# 3_TopLevel.net
KiCad netlist of a schematic drawn in Altium Designer
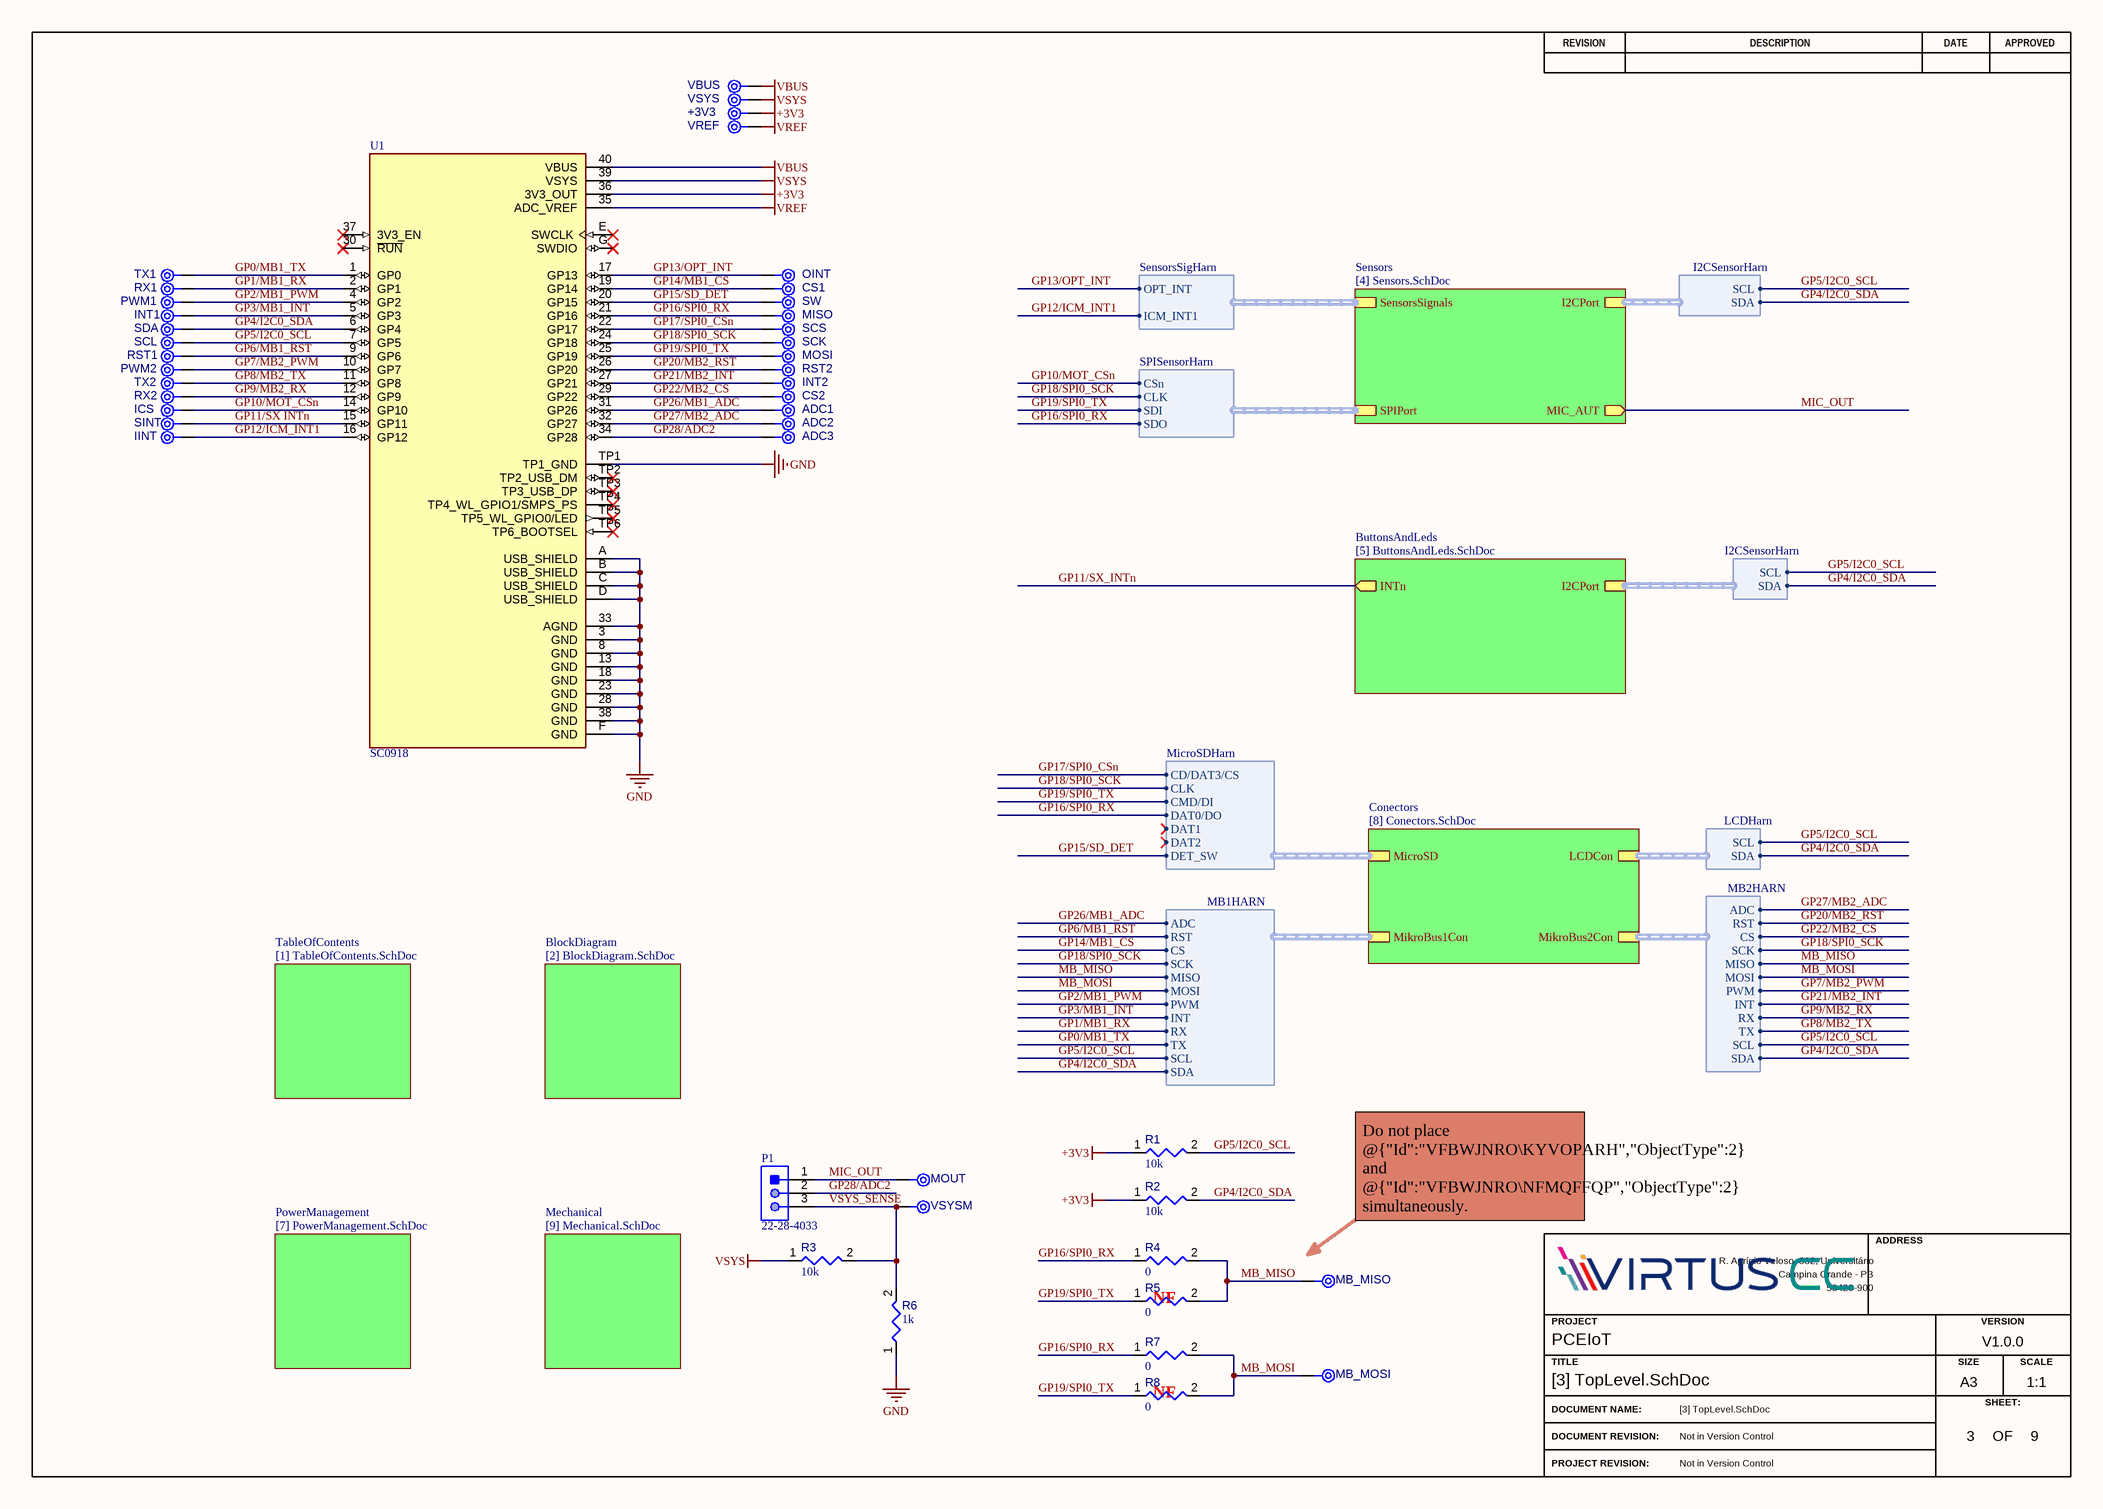
[diagram p0: [3] TopLevel.SchDoc]

(export (version "E")
  (design (tool "Eeschema 10.0.6"))
  (components
    (comp (ref "+3V3")
      (value "TPAD6R")
      (footprint "TP06R")
      (description "0.6mm round")
      (libsource (lib "PCEIOT") (part "CMP-00028-00002-2"))
    )
    (comp (ref "ADC1")
      (value "TPAD6R")
      (footprint "TP06R")
      (description "0.6mm round")
      (libsource (lib "PCEIOT") (part "CMP-00028-00002-2"))
    )
    (comp (ref "ADC2")
      (value "TPAD6R")
      (footprint "TP06R")
      (description "0.6mm round")
      (libsource (lib "PCEIOT") (part "CMP-00028-00002-2"))
    )
    (comp (ref "ADC3")
      (value "TPAD6R")
      (footprint "TP06R")
      (description "0.6mm round")
      (libsource (lib "PCEIOT") (part "CMP-00028-00002-2"))
    )
    (comp (ref "CS1")
      (value "TPAD6R")
      (footprint "TP06R")
      (description "0.6mm round")
      (libsource (lib "PCEIOT") (part "CMP-00028-00002-2"))
    )
    (comp (ref "CS2")
      (value "TPAD6R")
      (footprint "TP06R")
      (description "0.6mm round")
      (libsource (lib "PCEIOT") (part "CMP-00028-00002-2"))
    )
    (comp (ref "ICS")
      (value "TPAD6R")
      (footprint "TP06R")
      (description "0.6mm round")
      (libsource (lib "PCEIOT") (part "CMP-00028-00002-2"))
    )
    (comp (ref "IINT")
      (value "TPAD6R")
      (footprint "TP06R")
      (description "0.6mm round")
      (libsource (lib "PCEIOT") (part "CMP-00028-00002-2"))
    )
    (comp (ref "INT1")
      (value "TPAD6R")
      (footprint "TP06R")
      (description "0.6mm round")
      (libsource (lib "PCEIOT") (part "CMP-00028-00002-2"))
    )
    (comp (ref "INT2")
      (value "TPAD6R")
      (footprint "TP06R")
      (description "0.6mm round")
      (libsource (lib "PCEIOT") (part "CMP-00028-00002-2"))
    )
    (comp (ref "MB_MISO")
      (value "TPAD6R")
      (footprint "TP06R")
      (description "0.6mm round")
      (libsource (lib "PCEIOT") (part "CMP-00028-00002-2"))
    )
    (comp (ref "MB_MOSI")
      (value "TPAD6R")
      (footprint "TP06R")
      (description "0.6mm round")
      (libsource (lib "PCEIOT") (part "CMP-00028-00002-2"))
    )
    (comp (ref "MISO")
      (value "TPAD6R")
      (footprint "TP06R")
      (description "0.6mm round")
      (libsource (lib "PCEIOT") (part "CMP-00028-00002-2"))
    )
    (comp (ref "MOSI")
      (value "TPAD6R")
      (footprint "TP06R")
      (description "0.6mm round")
      (libsource (lib "PCEIOT") (part "CMP-00028-00002-2"))
    )
    (comp (ref "MOUT")
      (value "TPAD6R")
      (footprint "TP06R")
      (description "0.6mm round")
      (libsource (lib "PCEIOT") (part "CMP-00028-00002-2"))
    )
    (comp (ref "OINT")
      (value "TPAD6R")
      (footprint "TP06R")
      (description "0.6mm round")
      (libsource (lib "PCEIOT") (part "CMP-00028-00002-2"))
    )
    (comp (ref "P1")
      (value "22-28-4033")
      (footprint "MOLX-22-28-4033_V")
      (description "KK 254 Breakaway Header Vertical 3 Circuits 0.38um Gold Selective Plating Mating Pin 6.09mm")
      (libsource (lib "UFCG - Universidade Federal de Campina Grande") (part "CN-1P-M-R3"))
    )
    (comp (ref "PWM1")
      (value "TPAD6R")
      (footprint "TP06R")
      (description "0.6mm round")
      (libsource (lib "PCEIOT") (part "CMP-00028-00002-2"))
    )
    (comp (ref "PWM2")
      (value "TPAD6R")
      (footprint "TP06R")
      (description "0.6mm round")
      (libsource (lib "PCEIOT") (part "CMP-00028-00002-2"))
    )
    (comp (ref "R1")
      (value "10k")
      (footprint "RESC0603(1608)_L")
      (description "Chip Resistor, 10 KOhm, +/- 1%, 01 W, -55 to 155 degC, 0603 (1608 Metric)")
      (fields (field (name "POWER") "100mW") (field (name "TOLERANCE") "1%"))
      (libsource (lib "UFCG - Universidade Federal de Campina Grande") (part "RES-2"))
    )
    (comp (ref "R2")
      (value "10k")
      (footprint "RESC0603(1608)_L")
      (description "Chip Resistor, 10 KOhm, +/- 1%, 01 W, -55 to 155 degC, 0603 (1608 Metric)")
      (fields (field (name "POWER") "100mW") (field (name "TOLERANCE") "1%"))
      (libsource (lib "UFCG - Universidade Federal de Campina Grande") (part "RES-2"))
    )
    (comp (ref "R3")
      (value "10k")
      (footprint "RESC0603(1608)_L")
      (description "Chip Resistor, 10 KOhm, +/- 1%, 01 W, -55 to 155 degC, 0603 (1608 Metric)")
      (fields (field (name "POWER") "100mW") (field (name "TOLERANCE") "1%"))
      (libsource (lib "UFCG - Universidade Federal de Campina Grande") (part "RES-2"))
    )
    (comp (ref "R4")
      (value "0")
      (footprint "RESC0603(1608)_L")
      (description "Chip Resistor, 0 Ohm, 0.1 W, -55 to 155 degC, 0603 (1608 Metric)")
      (fields (field (name "TOLERANCE") "5%") (field (name "POWER") "100mW"))
      (libsource (lib "UFCG - Universidade Federal de Campina Grande") (part "RES-2"))
    )
    (comp (ref "R5")
      (value "0")
      (footprint "RESC0603(1608)_L")
      (description "Chip Resistor, 0 Ohm, 0.1 W, -55 to 155 degC, 0603 (1608 Metric)")
      (fields (field (name "TOLERANCE") "5%") (field (name "POWER") "100mW"))
      (libsource (lib "UFCG - Universidade Federal de Campina Grande") (part "RES-2"))
    )
    (comp (ref "R6")
      (value "1k")
      (footprint "RESC0603(1608)_L")
      (description "Chip Resistor, 1 KOhm, +/-1%, 0.1 W, -55 to 155 degC, 0603 (1608 Metric)")
      (fields (field (name "POWER") "100mW") (field (name "TOLERANCE") "1%"))
      (libsource (lib "UFCG - Universidade Federal de Campina Grande") (part "RES-2"))
    )
    (comp (ref "R7")
      (value "0")
      (footprint "RESC0603(1608)_L")
      (description "Chip Resistor, 0 Ohm, 0.1 W, -55 to 155 degC, 0603 (1608 Metric)")
      (fields (field (name "TOLERANCE") "5%") (field (name "POWER") "100mW"))
      (libsource (lib "UFCG - Universidade Federal de Campina Grande") (part "RES-2"))
    )
    (comp (ref "R8")
      (value "0")
      (footprint "RESC0603(1608)_L")
      (description "Chip Resistor, 0 Ohm, 0.1 W, -55 to 155 degC, 0603 (1608 Metric)")
      (fields (field (name "TOLERANCE") "5%") (field (name "POWER") "100mW"))
      (libsource (lib "UFCG - Universidade Federal de Campina Grande") (part "RES-2"))
    )
    (comp (ref "RST1")
      (value "TPAD6R")
      (footprint "TP06R")
      (description "0.6mm round")
      (libsource (lib "PCEIOT") (part "CMP-00028-00002-2"))
    )
    (comp (ref "RST2")
      (value "TPAD6R")
      (footprint "TP06R")
      (description "0.6mm round")
      (libsource (lib "PCEIOT") (part "CMP-00028-00002-2"))
    )
    (comp (ref "RX1")
      (value "TPAD6R")
      (footprint "TP06R")
      (description "0.6mm round")
      (libsource (lib "PCEIOT") (part "CMP-00028-00002-2"))
    )
    (comp (ref "RX2")
      (value "TPAD6R")
      (footprint "TP06R")
      (description "0.6mm round")
      (libsource (lib "PCEIOT") (part "CMP-00028-00002-2"))
    )
    (comp (ref "SCK")
      (value "TPAD6R")
      (footprint "TP06R")
      (description "0.6mm round")
      (libsource (lib "PCEIOT") (part "CMP-00028-00002-2"))
    )
    (comp (ref "SCL")
      (value "TPAD6R")
      (footprint "TP06R")
      (description "0.6mm round")
      (libsource (lib "PCEIOT") (part "CMP-00028-00002-2"))
    )
    (comp (ref "SCS")
      (value "TPAD6R")
      (footprint "TP06R")
      (description "0.6mm round")
      (libsource (lib "PCEIOT") (part "CMP-00028-00002-2"))
    )
    (comp (ref "SDA")
      (value "TPAD6R")
      (footprint "TP06R")
      (description "0.6mm round")
      (libsource (lib "PCEIOT") (part "CMP-00028-00002-2"))
    )
    (comp (ref "SINT")
      (value "TPAD6R")
      (footprint "TP06R")
      (description "0.6mm round")
      (libsource (lib "PCEIOT") (part "CMP-00028-00002-2"))
    )
    (comp (ref "SW")
      (value "TPAD6R")
      (footprint "TP06R")
      (description "0.6mm round")
      (libsource (lib "PCEIOT") (part "CMP-00028-00002-2"))
    )
    (comp (ref "TX1")
      (value "TPAD6R")
      (footprint "TP06R")
      (description "0.6mm round")
      (libsource (lib "PCEIOT") (part "CMP-00028-00002-2"))
    )
    (comp (ref "TX2")
      (value "TPAD6R")
      (footprint "TP06R")
      (description "0.6mm round")
      (libsource (lib "PCEIOT") (part "CMP-00028-00002-2"))
    )
    (comp (ref "U1")
      (value "SC0918")
      (footprint "MODULE_SC0918")
      (description "Raspberry Pi Pico W RP2040")
      (fields (field (name "MF") "Raspberry Pi"))
      (libsource (lib "UFCG - Universidade Federal de Campina Grande") (part "SC0918"))
    )
    (comp (ref "VBUS")
      (value "TPAD6R")
      (footprint "TP06R")
      (description "0.6mm round")
      (libsource (lib "PCEIOT") (part "CMP-00028-00002-2"))
    )
    (comp (ref "VREF")
      (value "TPAD6R")
      (footprint "TP06R")
      (description "0.6mm round")
      (libsource (lib "PCEIOT") (part "CMP-00028-00002-2"))
    )
    (comp (ref "VSYS")
      (value "TPAD6R")
      (footprint "TP06R")
      (description "0.6mm round")
      (libsource (lib "PCEIOT") (part "CMP-00028-00002-2"))
    )
    (comp (ref "VSYSM")
      (value "TPAD6R")
      (footprint "TP06R")
      (description "0.6mm round")
      (libsource (lib "PCEIOT") (part "CMP-00028-00002-2"))
    )
  )
  (nets
    (net (code "8") (name "+3V3") (class "Default")
      (node (ref "+3V3") (pin "1") (pinfunction "TP_1") (pintype "passive"))
      (node (ref "R1") (pin "1") (pinfunction "1_1") (pintype "passive"))
      (node (ref "R2") (pin "1") (pinfunction "1_1") (pintype "passive"))
      (node (ref "U1") (pin "36") (pinfunction "3V3_OUT_36") (pintype "power_in"))
    )
    (net (code "9") (name "/GP0{slash}MB1_TX") (class "Default")
      (node (ref "TX1") (pin "1") (pinfunction "TP_1") (pintype "passive"))
      (node (ref "U1") (pin "1") (pinfunction "GP0_1") (pintype "bidirectional"))
    )
    (net (code "10") (name "/GP1{slash}MB1_RX") (class "Default")
      (node (ref "RX1") (pin "1") (pinfunction "TP_1") (pintype "passive"))
      (node (ref "U1") (pin "2") (pinfunction "GP1_2") (pintype "bidirectional"))
    )
    (net (code "11") (name "/GP2{slash}MB1_PWM") (class "Default")
      (node (ref "PWM1") (pin "1") (pinfunction "TP_1") (pintype "passive"))
      (node (ref "U1") (pin "4") (pinfunction "GP2_4") (pintype "bidirectional"))
    )
    (net (code "12") (name "/GP3{slash}MB1_INT") (class "Default")
      (node (ref "INT1") (pin "1") (pinfunction "TP_1") (pintype "passive"))
      (node (ref "U1") (pin "5") (pinfunction "GP3_5") (pintype "bidirectional"))
    )
    (net (code "13") (name "/GP4{slash}I2C0_SDA") (class "Default")
      (node (ref "R2") (pin "2") (pinfunction "2_2") (pintype "passive"))
      (node (ref "SDA") (pin "1") (pinfunction "TP_1") (pintype "passive"))
      (node (ref "U1") (pin "6") (pinfunction "GP4_6") (pintype "bidirectional"))
    )
    (net (code "14") (name "/GP5{slash}I2C0_SCL") (class "Default")
      (node (ref "R1") (pin "2") (pinfunction "2_2") (pintype "passive"))
      (node (ref "SCL") (pin "1") (pinfunction "TP_1") (pintype "passive"))
      (node (ref "U1") (pin "7") (pinfunction "GP5_7") (pintype "bidirectional"))
    )
    (net (code "15") (name "/GP6{slash}MB1_RST") (class "Default")
      (node (ref "RST1") (pin "1") (pinfunction "TP_1") (pintype "passive"))
      (node (ref "U1") (pin "9") (pinfunction "GP6_9") (pintype "bidirectional"))
    )
    (net (code "16") (name "/GP7{slash}MB2_PWM") (class "Default")
      (node (ref "PWM2") (pin "1") (pinfunction "TP_1") (pintype "passive"))
      (node (ref "U1") (pin "10") (pinfunction "GP7_10") (pintype "bidirectional"))
    )
    (net (code "17") (name "/GP8{slash}MB2_TX") (class "Default")
      (node (ref "TX2") (pin "1") (pinfunction "TP_1") (pintype "passive"))
      (node (ref "U1") (pin "11") (pinfunction "GP8_11") (pintype "bidirectional"))
    )
    (net (code "18") (name "/GP9{slash}MB2_RX") (class "Default")
      (node (ref "RX2") (pin "1") (pinfunction "TP_1") (pintype "passive"))
      (node (ref "U1") (pin "12") (pinfunction "GP9_12") (pintype "bidirectional"))
    )
    (net (code "19") (name "/GP10{slash}MOT_CSn") (class "Default")
      (node (ref "ICS") (pin "1") (pinfunction "TP_1") (pintype "passive"))
      (node (ref "U1") (pin "14") (pinfunction "GP10_14") (pintype "bidirectional"))
    )
    (net (code "20") (name "/GP11{slash}SX INTn") (class "Default")
      (node (ref "SINT") (pin "1") (pinfunction "TP_1") (pintype "passive"))
      (node (ref "U1") (pin "15") (pinfunction "GP11_15") (pintype "bidirectional"))
    )
    (net (code "22") (name "/GP12{slash}ICM_INT1") (class "Default")
      (node (ref "IINT") (pin "1") (pinfunction "TP_1") (pintype "passive"))
      (node (ref "U1") (pin "16") (pinfunction "GP12_16") (pintype "bidirectional"))
    )
    (net (code "23") (name "/GP13{slash}OPT_INT") (class "Default")
      (node (ref "OINT") (pin "1") (pinfunction "TP_1") (pintype "passive"))
      (node (ref "U1") (pin "17") (pinfunction "GP13_17") (pintype "bidirectional"))
    )
    (net (code "24") (name "/GP14{slash}MB1_CS") (class "Default")
      (node (ref "CS1") (pin "1") (pinfunction "TP_1") (pintype "passive"))
      (node (ref "U1") (pin "19") (pinfunction "GP14_19") (pintype "bidirectional"))
    )
    (net (code "25") (name "/GP15{slash}SD_DET") (class "Default")
      (node (ref "SW") (pin "1") (pinfunction "TP_1") (pintype "passive"))
      (node (ref "U1") (pin "20") (pinfunction "GP15_20") (pintype "bidirectional"))
    )
    (net (code "26") (name "/GP16{slash}SPI0_RX") (class "Default")
      (node (ref "MISO") (pin "1") (pinfunction "TP_1") (pintype "passive"))
      (node (ref "R4") (pin "1") (pinfunction "1_1") (pintype "passive"))
      (node (ref "R7") (pin "1") (pinfunction "1_1") (pintype "passive"))
      (node (ref "U1") (pin "21") (pinfunction "GP16_21") (pintype "bidirectional"))
    )
    (net (code "27") (name "/GP17{slash}SPI0_CSn") (class "Default")
      (node (ref "SCS") (pin "1") (pinfunction "TP_1") (pintype "passive"))
      (node (ref "U1") (pin "22") (pinfunction "GP17_22") (pintype "bidirectional"))
    )
    (net (code "28") (name "/GP18{slash}SPI0_SCK") (class "Default")
      (node (ref "SCK") (pin "1") (pinfunction "TP_1") (pintype "passive"))
      (node (ref "U1") (pin "24") (pinfunction "GP18_24") (pintype "bidirectional"))
    )
    (net (code "29") (name "/GP19{slash}SPI0_TX") (class "Default")
      (node (ref "MOSI") (pin "1") (pinfunction "TP_1") (pintype "passive"))
      (node (ref "R5") (pin "1") (pinfunction "1_1") (pintype "passive"))
      (node (ref "R8") (pin "1") (pinfunction "1_1") (pintype "passive"))
      (node (ref "U1") (pin "25") (pinfunction "GP19_25") (pintype "bidirectional"))
    )
    (net (code "30") (name "/GP20{slash}MB2_RST") (class "Default")
      (node (ref "RST2") (pin "1") (pinfunction "TP_1") (pintype "passive"))
      (node (ref "U1") (pin "26") (pinfunction "GP20_26") (pintype "bidirectional"))
    )
    (net (code "31") (name "/GP21{slash}MB2_INT") (class "Default")
      (node (ref "INT2") (pin "1") (pinfunction "TP_1") (pintype "passive"))
      (node (ref "U1") (pin "27") (pinfunction "GP21_27") (pintype "bidirectional"))
    )
    (net (code "32") (name "/GP22{slash}MB2_CS") (class "Default")
      (node (ref "CS2") (pin "1") (pinfunction "TP_1") (pintype "passive"))
      (node (ref "U1") (pin "29") (pinfunction "GP22_29") (pintype "bidirectional"))
    )
    (net (code "33") (name "/GP26{slash}MB1_ADC") (class "Default")
      (node (ref "ADC1") (pin "1") (pinfunction "TP_1") (pintype "passive"))
      (node (ref "U1") (pin "31") (pinfunction "GP26_31") (pintype "bidirectional"))
    )
    (net (code "34") (name "/GP27{slash}MB2_ADC") (class "Default")
      (node (ref "ADC2") (pin "1") (pinfunction "TP_1") (pintype "passive"))
      (node (ref "U1") (pin "32") (pinfunction "GP27_32") (pintype "bidirectional"))
    )
    (net (code "35") (name "/GP28{slash}ADC2") (class "Default")
      (node (ref "ADC3") (pin "1") (pinfunction "TP_1") (pintype "passive"))
      (node (ref "P1") (pin "2") (pinfunction "2_2") (pintype "passive"))
      (node (ref "U1") (pin "34") (pinfunction "GP28_34") (pintype "bidirectional"))
    )
    (net (code "36") (name "/MB_MISO") (class "Default")
      (node (ref "MB_MISO") (pin "1") (pinfunction "TP_1") (pintype "passive"))
      (node (ref "R4") (pin "2") (pinfunction "2_2") (pintype "passive"))
      (node (ref "R5") (pin "2") (pinfunction "2_2") (pintype "passive"))
    )
    (net (code "37") (name "/MB_MOSI") (class "Default")
      (node (ref "MB_MOSI") (pin "1") (pinfunction "TP_1") (pintype "passive"))
      (node (ref "R7") (pin "2") (pinfunction "2_2") (pintype "passive"))
      (node (ref "R8") (pin "2") (pinfunction "2_2") (pintype "passive"))
    )
    (net (code "38") (name "/MIC_OUT") (class "Default")
      (node (ref "MOUT") (pin "1") (pinfunction "TP_1") (pintype "passive"))
      (node (ref "P1") (pin "1") (pinfunction "1_1") (pintype "passive"))
    )
    (net (code "39") (name "/VSYS_SENSE") (class "Default")
      (node (ref "P1") (pin "3") (pinfunction "3_3") (pintype "passive"))
      (node (ref "R3") (pin "2") (pinfunction "2_2") (pintype "passive"))
      (node (ref "R6") (pin "2") (pinfunction "2_2") (pintype "passive"))
      (node (ref "VSYSM") (pin "1") (pinfunction "TP_1") (pintype "passive"))
    )
    (net (code "47") (name "GND") (class "Default")
      (node (ref "R6") (pin "1") (pinfunction "1_1") (pintype "passive"))
      (node (ref "U1") (pin "13") (pinfunction "GND_13") (pintype "power_in"))
      (node (ref "U1") (pin "18") (pinfunction "GND_18") (pintype "power_in"))
      (node (ref "U1") (pin "23") (pinfunction "GND_23") (pintype "power_in"))
      (node (ref "U1") (pin "28") (pinfunction "GND_28") (pintype "power_in"))
      (node (ref "U1") (pin "3") (pinfunction "GND_3") (pintype "power_in"))
      (node (ref "U1") (pin "33") (pinfunction "AGND_33") (pintype "power_in"))
      (node (ref "U1") (pin "38") (pinfunction "GND_38") (pintype "power_in"))
      (node (ref "U1") (pin "8") (pinfunction "GND_8") (pintype "power_in"))
      (node (ref "U1") (pin "A") (pinfunction "USB_SHIELD_A") (pintype "power_in"))
      (node (ref "U1") (pin "B") (pinfunction "USB_SHIELD_B") (pintype "power_in"))
      (node (ref "U1") (pin "C") (pinfunction "USB_SHIELD_C") (pintype "power_in"))
      (node (ref "U1") (pin "D") (pinfunction "USB_SHIELD_D") (pintype "power_in"))
      (node (ref "U1") (pin "F") (pinfunction "GND_F") (pintype "power_in"))
      (node (ref "U1") (pin "TP1") (pinfunction "TP1_GND_TP1") (pintype "power_in"))
    )
    (net (code "48") (name "VBUS") (class "Default")
      (node (ref "U1") (pin "40") (pinfunction "VBUS_40") (pintype "power_in"))
      (node (ref "VBUS") (pin "1") (pinfunction "TP_1") (pintype "passive"))
    )
    (net (code "49") (name "VREF") (class "Default")
      (node (ref "U1") (pin "35") (pinfunction "ADC_VREF_35") (pintype "power_in"))
      (node (ref "VREF") (pin "1") (pinfunction "TP_1") (pintype "passive"))
    )
    (net (code "50") (name "VSYS") (class "Default")
      (node (ref "R3") (pin "1") (pinfunction "1_1") (pintype "passive"))
      (node (ref "U1") (pin "39") (pinfunction "VSYS_39") (pintype "power_in"))
      (node (ref "VSYS") (pin "1") (pinfunction "TP_1") (pintype "passive"))
    )
    (net (code "51") (name "unconnected-(U1-3V3_EN-Pad37)") (class "Default")
      (node (ref "U1") (pin "37") (pinfunction "3V3_EN_37") (pintype "input+no_connect"))
    )
    (net (code "52") (name "unconnected-(U1-SWCLK-PadE)") (class "Default")
      (node (ref "U1") (pin "E") (pinfunction "SWCLK_E") (pintype "input+no_connect"))
    )
    (net (code "53") (name "unconnected-(U1-SWDIO-PadG)") (class "Default")
      (node (ref "U1") (pin "G") (pinfunction "SWDIO_G") (pintype "bidirectional+no_connect"))
    )
    (net (code "54") (name "unconnected-(U1-TP2_USB_DM-PadTP2)") (class "Default")
      (node (ref "U1") (pin "TP2") (pinfunction "TP2_USB_DM_TP2") (pintype "bidirectional+no_connect"))
    )
    (net (code "55") (name "unconnected-(U1-TP3_USB_DP-PadTP3)") (class "Default")
      (node (ref "U1") (pin "TP3") (pinfunction "TP3_USB_DP_TP3") (pintype "bidirectional+no_connect"))
    )
    (net (code "56") (name "unconnected-(U1-TP4_WL_GPIO1{slash}SMPS_PS-PadTP4)") (class "Default")
      (node (ref "U1") (pin "TP4") (pinfunction "TP4_WL_GPIO1/SMPS_PS_TP4") (pintype "passive+no_connect"))
    )
    (net (code "57") (name "unconnected-(U1-TP5_WL_GPIO0{slash}LED-PadTP5)") (class "Default")
      (node (ref "U1") (pin "TP5") (pinfunction "TP5_WL_GPIO0/LED_TP5") (pintype "output+no_connect"))
    )
    (net (code "58") (name "unconnected-(U1-TP6_BOOTSEL-PadTP6)") (class "Default")
      (node (ref "U1") (pin "TP6") (pinfunction "TP6_BOOTSEL_TP6") (pintype "input+no_connect"))
    )
    (net (code "59") (name "unconnected-(U1-~{RUN}-Pad30)") (class "Default")
      (node (ref "U1") (pin "30") (pinfunction "~{RUN}_30") (pintype "input+no_connect"))
    )
  )
)
